# multi-rc522.net
KiCad netlist of a schematic drawn in Altium Designer
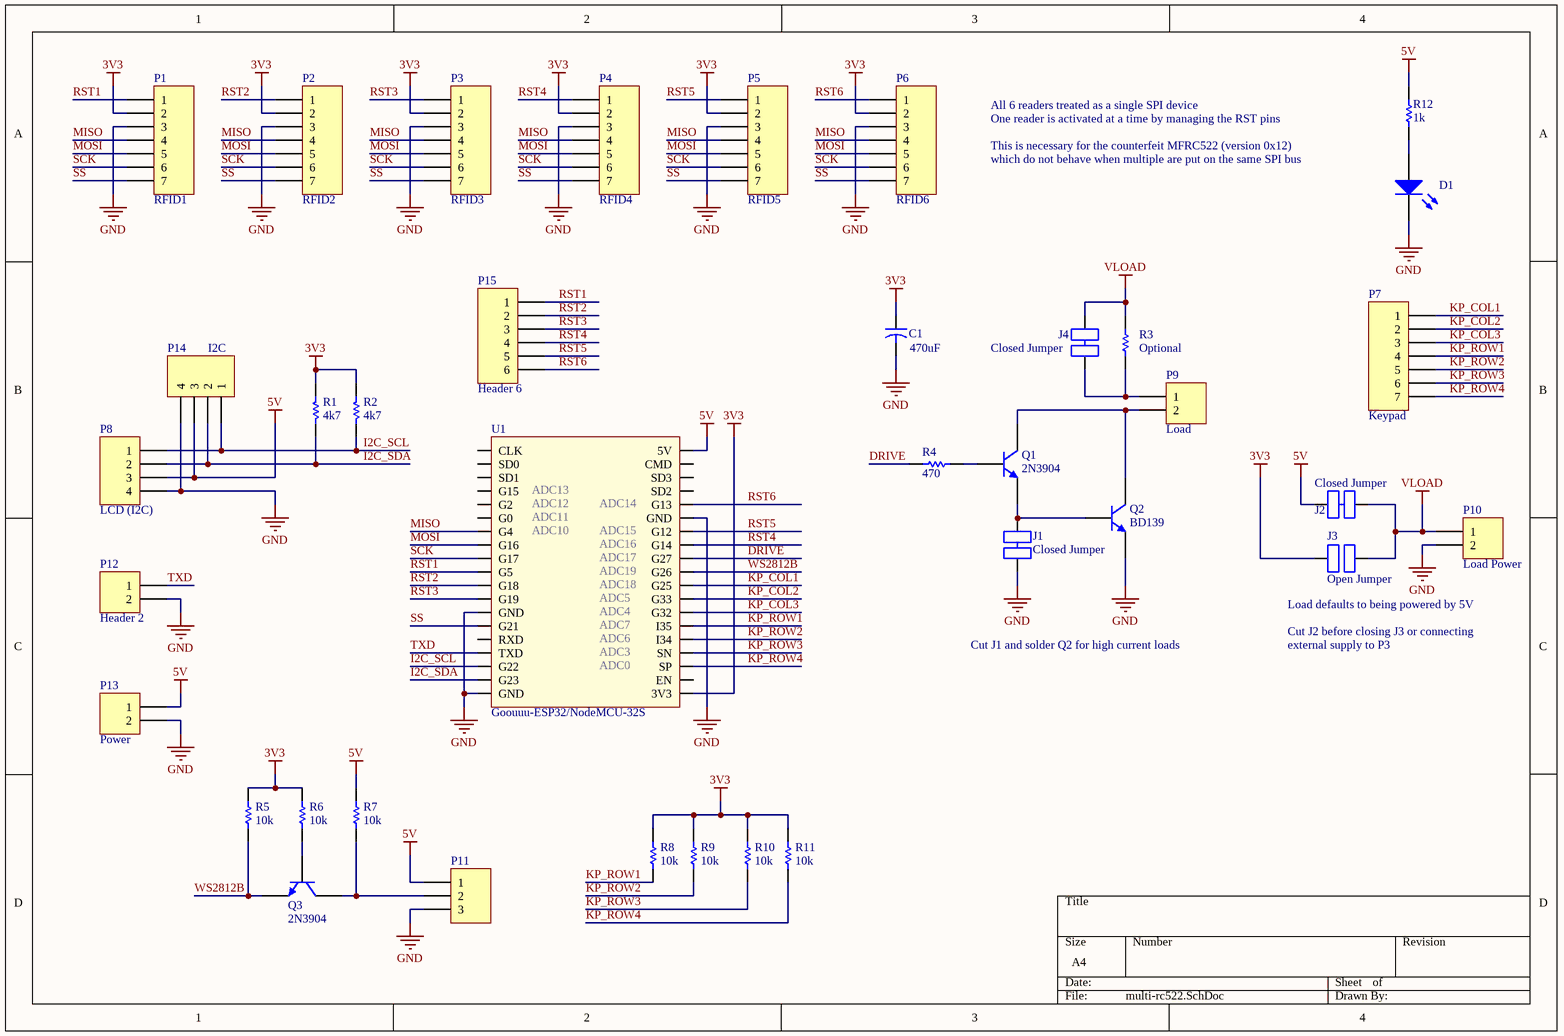
[diagram p0: multi-rc522.SchDoc]

(export (version "E")
  (design (tool "Eeschema 10.0.6"))
  (components
    (comp (ref "C1")
      (value "470uF")
      (footprint "CAPR5-4X5")
      (description "Capacitor")
      (fields (field (name "Comment") "Cap2") (field (name "PUBLISHER") "Altium Limited"))
      (libsource (lib "Miscellaneous Devices") (part "Cap2"))
    )
    (comp (ref "D1")
      (value "LED")
      (footprint "LED")
      (fields (field (name "PUBLISHER") "Altium Limited"))
      (libsource (lib "components") (part "LED"))
    )
    (comp (ref "J1")
      (value "Closed Jumper")
      (footprint "Jumper (Close)")
      (libsource (lib "components") (part "Jumper (Closed)"))
    )
    (comp (ref "J2")
      (value "Closed Jumper")
      (footprint "Jumper (Close)")
      (libsource (lib "components") (part "Jumper (Closed)"))
    )
    (comp (ref "J3")
      (value "Open Jumper")
      (footprint "Jumper (Open)")
      (libsource (lib "components") (part "Jumper (Open)"))
    )
    (comp (ref "J4")
      (value "Closed Jumper")
      (footprint "Jumper (Close)")
      (libsource (lib "components") (part "Jumper (Closed)"))
    )
    (comp (ref "P1")
      (value "RFID1")
      (footprint "HDR1X7")
      (description "Header, 7-Pin")
      (fields (field (name "PUBLISHER") "Altium Limited"))
      (libsource (lib "Miscellaneous Connectors") (part "Header 7"))
    )
    (comp (ref "P2")
      (value "RFID2")
      (footprint "HDR1X7")
      (description "Header, 7-Pin")
      (fields (field (name "PUBLISHER") "Altium Limited"))
      (libsource (lib "Miscellaneous Connectors") (part "Header 7"))
    )
    (comp (ref "P3")
      (value "RFID3")
      (footprint "HDR1X7")
      (description "Header, 7-Pin")
      (fields (field (name "PUBLISHER") "Altium Limited"))
      (libsource (lib "Miscellaneous Connectors") (part "Header 7"))
    )
    (comp (ref "P4")
      (value "RFID4")
      (footprint "HDR1X7")
      (description "Header, 7-Pin")
      (fields (field (name "PUBLISHER") "Altium Limited"))
      (libsource (lib "Miscellaneous Connectors") (part "Header 7"))
    )
    (comp (ref "P5")
      (value "RFID5")
      (footprint "HDR1X7")
      (description "Header, 7-Pin")
      (fields (field (name "PUBLISHER") "Altium Limited"))
      (libsource (lib "Miscellaneous Connectors") (part "Header 7"))
    )
    (comp (ref "P6")
      (value "RFID6")
      (footprint "HDR1X7")
      (description "Header, 7-Pin")
      (fields (field (name "PUBLISHER") "Altium Limited"))
      (libsource (lib "Miscellaneous Connectors") (part "Header 7"))
    )
    (comp (ref "P7")
      (value "Keypad")
      (footprint "HDR1X7")
      (description "Header, 7-Pin")
      (fields (field (name "PUBLISHER") "Altium Limited"))
      (libsource (lib "") (part "Header 7_1"))
    )
    (comp (ref "P8")
      (value "LCD (I2C)")
      (footprint "HDR1X4")
      (description "Header, 4-Pin")
      (fields (field (name "PUBLISHER") "Altium Limited"))
      (libsource (lib "Miscellaneous Connectors") (part "Header 4"))
    )
    (comp (ref "P9")
      (value "Load")
      (footprint "RAD-0.2")
      (description "Header, 2-Pin")
      (fields (field (name "PUBLISHER") "Altium Limited"))
      (libsource (lib "Miscellaneous Connectors") (part "Header 2"))
    )
    (comp (ref "P10")
      (value "Load Power")
      (footprint "RAD-0.2")
      (description "Header, 2-Pin")
      (fields (field (name "PUBLISHER") "Altium Limited"))
      (libsource (lib "Miscellaneous Connectors") (part "Header 2"))
    )
    (comp (ref "P11")
      (value "Header 3")
      (footprint "HDR1X3")
      (description "Header, 3-Pin")
      (fields (field (name "PUBLISHER") "Altium Limited"))
      (libsource (lib "Miscellaneous Connectors") (part "Header 3"))
    )
    (comp (ref "P12")
      (value "Header 2")
      (footprint "HDR1X2")
      (description "Header, 2-Pin")
      (fields (field (name "PUBLISHER") "Altium Limited"))
      (libsource (lib "") (part "Header 2_1"))
    )
    (comp (ref "P13")
      (value "Power")
      (footprint "RAD-0.2")
      (description "Header, 2-Pin")
      (fields (field (name "PUBLISHER") "Altium Limited"))
      (libsource (lib "") (part "Header 2_1"))
    )
    (comp (ref "P14")
      (value "I2C")
      (footprint "HDR1X4")
      (description "Header, 4-Pin")
      (fields (field (name "PUBLISHER") "Altium Limited"))
      (libsource (lib "") (part "Header 4_1"))
    )
    (comp (ref "P15")
      (value "Header 6")
      (footprint "HDR1X6")
      (description "Header, 6-Pin")
      (fields (field (name "PUBLISHER") "Altium Limited"))
      (libsource (lib "Miscellaneous Connectors") (part "Header 6"))
    )
    (comp (ref "Q1")
      (value "2N3904")
      (footprint "TO-92A")
      (description "NPN General Purpose Amplifier")
      (fields (field (name "PUBLISHER") "Altium Limited"))
      (libsource (lib "components") (part "2N3904"))
    )
    (comp (ref "Q2")
      (value "BD139")
      (footprint "Miscellaneous Devices:TO-220-AB")
      (description "NPN General Purpose Amplifier")
      (fields (field (name "PUBLISHER") "Altium Limited"))
      (libsource (lib "Miscellaneous Devices") (part "2N3904"))
    )
    (comp (ref "Q3")
      (value "2N3904")
      (footprint "TO-92A")
      (description "NPN General Purpose Amplifier")
      (fields (field (name "PUBLISHER") "Altium Limited"))
      (libsource (lib "components") (part "2N3904"))
    )
    (comp (ref "R1")
      (value "4k7")
      (footprint "Miscellaneous Devices:AXIAL-0.4")
      (description "Resistor")
      (fields (field (name "Comment") "Res1") (field (name "PUBLISHER") "Altium Limited"))
      (libsource (lib "Miscellaneous Devices") (part "Res1"))
    )
    (comp (ref "R2")
      (value "4k7")
      (footprint "Miscellaneous Devices:AXIAL-0.4")
      (description "Resistor")
      (fields (field (name "Comment") "Res1") (field (name "PUBLISHER") "Altium Limited"))
      (libsource (lib "Miscellaneous Devices") (part "Res1"))
    )
    (comp (ref "R3")
      (value "Optional")
      (footprint "Miscellaneous Devices:AXIAL-0.4")
      (description "Resistor")
      (fields (field (name "PUBLISHER") "Altium Limited"))
      (libsource (lib "Miscellaneous Devices") (part "Res1"))
    )
    (comp (ref "R4")
      (value "470")
      (footprint "Miscellaneous Devices:AXIAL-0.4")
      (description "Resistor")
      (fields (field (name "Comment") "Res1") (field (name "PUBLISHER") "Altium Limited"))
      (libsource (lib "Miscellaneous Devices") (part "Res1"))
    )
    (comp (ref "R5")
      (value "10k")
      (footprint "Miscellaneous Devices:RAD-0.1")
      (description "Resistor")
      (fields (field (name "Comment") "Res1") (field (name "PUBLISHER") "Altium Limited"))
      (libsource (lib "Miscellaneous Devices") (part "Res1"))
    )
    (comp (ref "R6")
      (value "10k")
      (footprint "Miscellaneous Devices:RAD-0.1")
      (description "Resistor")
      (fields (field (name "Comment") "Res1") (field (name "PUBLISHER") "Altium Limited"))
      (libsource (lib "Miscellaneous Devices") (part "Res1"))
    )
    (comp (ref "R7")
      (value "10k")
      (footprint "Miscellaneous Devices:RAD-0.1")
      (description "Resistor")
      (fields (field (name "Comment") "Res1") (field (name "PUBLISHER") "Altium Limited"))
      (libsource (lib "Miscellaneous Devices") (part "Res1"))
    )
    (comp (ref "R8")
      (value "10k")
      (footprint "Miscellaneous Devices:RAD-0.1")
      (description "Resistor")
      (fields (field (name "Comment") "Res1") (field (name "PUBLISHER") "Altium Limited"))
      (libsource (lib "Miscellaneous Devices") (part "Res1"))
    )
    (comp (ref "R9")
      (value "10k")
      (footprint "Miscellaneous Devices:RAD-0.1")
      (description "Resistor")
      (fields (field (name "Comment") "Res1") (field (name "PUBLISHER") "Altium Limited"))
      (libsource (lib "Miscellaneous Devices") (part "Res1"))
    )
    (comp (ref "R10")
      (value "10k")
      (footprint "Miscellaneous Devices:RAD-0.1")
      (description "Resistor")
      (fields (field (name "Comment") "Res1") (field (name "PUBLISHER") "Altium Limited"))
      (libsource (lib "Miscellaneous Devices") (part "Res1"))
    )
    (comp (ref "R11")
      (value "10k")
      (footprint "Miscellaneous Devices:RAD-0.1")
      (description "Resistor")
      (fields (field (name "Comment") "Res1") (field (name "PUBLISHER") "Altium Limited"))
      (libsource (lib "Miscellaneous Devices") (part "Res1"))
    )
    (comp (ref "R12")
      (value "1k")
      (footprint "Miscellaneous Devices:AXIAL-0.4")
      (description "Resistor")
      (fields (field (name "Comment") "Res1") (field (name "PUBLISHER") "Altium Limited"))
      (libsource (lib "Miscellaneous Devices") (part "Res1"))
    )
    (comp (ref "U1")
      (value "Goouuu-ESP32/NodeMCU-32S")
      (footprint "ESP32")
      (libsource (lib "components") (part "ESP32"))
    )
  )
  (nets
    (net (code "1") (name "/DRIVE") (class "Default")
      (node (ref "R4") (pin "2") (pinfunction "2_2") (pintype "passive"))
      (node (ref "U1") (pin "30") (pinfunction "G27_30") (pintype "passive"))
    )
    (net (code "2") (name "/I2C_SCL") (class "Default")
      (node (ref "P14") (pin "1") (pinfunction "1_1") (pintype "passive"))
      (node (ref "P8") (pin "1") (pinfunction "1_1") (pintype "passive"))
      (node (ref "R2") (pin "1") (pinfunction "1_1") (pintype "passive"))
      (node (ref "U1") (pin "17") (pinfunction "G22_17") (pintype "passive"))
    )
    (net (code "3") (name "/I2C_SDA") (class "Default")
      (node (ref "P14") (pin "2") (pinfunction "2_2") (pintype "passive"))
      (node (ref "P8") (pin "2") (pinfunction "2_2") (pintype "passive"))
      (node (ref "R1") (pin "1") (pinfunction "1_1") (pintype "passive"))
      (node (ref "U1") (pin "18") (pinfunction "G23_18") (pintype "passive"))
    )
    (net (code "4") (name "/KP_COL1") (class "Default")
      (node (ref "P7") (pin "1") (pinfunction "1_1") (pintype "passive"))
      (node (ref "U1") (pin "28") (pinfunction "G25_28") (pintype "passive"))
    )
    (net (code "5") (name "/KP_COL2") (class "Default")
      (node (ref "P7") (pin "2") (pinfunction "2_2") (pintype "passive"))
      (node (ref "U1") (pin "27") (pinfunction "G33_27") (pintype "passive"))
    )
    (net (code "6") (name "/KP_COL3") (class "Default")
      (node (ref "P7") (pin "3") (pinfunction "3_3") (pintype "passive"))
      (node (ref "U1") (pin "26") (pinfunction "G32_26") (pintype "passive"))
    )
    (net (code "7") (name "/KP_ROW1") (class "Default")
      (node (ref "P7") (pin "4") (pinfunction "4_4") (pintype "passive"))
      (node (ref "R8") (pin "1") (pinfunction "1_1") (pintype "passive"))
      (node (ref "U1") (pin "25") (pinfunction "I35_25") (pintype "passive"))
    )
    (net (code "8") (name "/KP_ROW2") (class "Default")
      (node (ref "P7") (pin "5") (pinfunction "5_5") (pintype "passive"))
      (node (ref "R9") (pin "1") (pinfunction "1_1") (pintype "passive"))
      (node (ref "U1") (pin "24") (pinfunction "I34_24") (pintype "passive"))
    )
    (net (code "9") (name "/KP_ROW3") (class "Default")
      (node (ref "P7") (pin "6") (pinfunction "6_6") (pintype "passive"))
      (node (ref "R10") (pin "1") (pinfunction "1_1") (pintype "passive"))
      (node (ref "U1") (pin "23") (pinfunction "SN_23") (pintype "passive"))
    )
    (net (code "10") (name "/KP_ROW4") (class "Default")
      (node (ref "P7") (pin "7") (pinfunction "7_7") (pintype "passive"))
      (node (ref "R11") (pin "1") (pinfunction "1_1") (pintype "passive"))
      (node (ref "U1") (pin "22") (pinfunction "SP_22") (pintype "passive"))
    )
    (net (code "11") (name "/MISO") (class "Default")
      (node (ref "P1") (pin "4") (pinfunction "4_4") (pintype "passive"))
      (node (ref "P2") (pin "4") (pinfunction "4_4") (pintype "passive"))
      (node (ref "P3") (pin "4") (pinfunction "4_4") (pintype "passive"))
      (node (ref "P4") (pin "4") (pinfunction "4_4") (pintype "passive"))
      (node (ref "P5") (pin "4") (pinfunction "4_4") (pintype "passive"))
      (node (ref "P6") (pin "4") (pinfunction "4_4") (pintype "passive"))
      (node (ref "U1") (pin "7") (pinfunction "G4_7") (pintype "passive"))
    )
    (net (code "12") (name "/MOSI") (class "Default")
      (node (ref "P1") (pin "5") (pinfunction "5_5") (pintype "passive"))
      (node (ref "P2") (pin "5") (pinfunction "5_5") (pintype "passive"))
      (node (ref "P3") (pin "5") (pinfunction "5_5") (pintype "passive"))
      (node (ref "P4") (pin "5") (pinfunction "5_5") (pintype "passive"))
      (node (ref "P5") (pin "5") (pinfunction "5_5") (pintype "passive"))
      (node (ref "P6") (pin "5") (pinfunction "5_5") (pintype "passive"))
      (node (ref "U1") (pin "8") (pinfunction "G16_8") (pintype "passive"))
    )
    (net (code "13") (name "/RST1") (class "Default")
      (node (ref "P1") (pin "1") (pinfunction "1_1") (pintype "passive"))
      (node (ref "P15") (pin "1") (pinfunction "1_1") (pintype "passive"))
      (node (ref "U1") (pin "10") (pinfunction "G5_10") (pintype "passive"))
    )
    (net (code "14") (name "/RST2") (class "Default")
      (node (ref "P15") (pin "2") (pinfunction "2_2") (pintype "passive"))
      (node (ref "P2") (pin "1") (pinfunction "1_1") (pintype "passive"))
      (node (ref "U1") (pin "11") (pinfunction "G18_11") (pintype "passive"))
    )
    (net (code "15") (name "/RST3") (class "Default")
      (node (ref "P15") (pin "3") (pinfunction "3_3") (pintype "passive"))
      (node (ref "P3") (pin "1") (pinfunction "1_1") (pintype "passive"))
      (node (ref "U1") (pin "12") (pinfunction "G19_12") (pintype "passive"))
    )
    (net (code "16") (name "/RST4") (class "Default")
      (node (ref "P15") (pin "4") (pinfunction "4_4") (pintype "passive"))
      (node (ref "P4") (pin "1") (pinfunction "1_1") (pintype "passive"))
      (node (ref "U1") (pin "31") (pinfunction "G14_31") (pintype "passive"))
    )
    (net (code "17") (name "/RST5") (class "Default")
      (node (ref "P15") (pin "5") (pinfunction "5_5") (pintype "passive"))
      (node (ref "P5") (pin "1") (pinfunction "1_1") (pintype "passive"))
      (node (ref "U1") (pin "32") (pinfunction "G12_32") (pintype "passive"))
    )
    (net (code "18") (name "/RST6") (class "Default")
      (node (ref "P15") (pin "6") (pinfunction "6_6") (pintype "passive"))
      (node (ref "P6") (pin "1") (pinfunction "1_1") (pintype "passive"))
      (node (ref "U1") (pin "34") (pinfunction "G13_34") (pintype "passive"))
    )
    (net (code "19") (name "/SCK") (class "Default")
      (node (ref "P1") (pin "6") (pinfunction "6_6") (pintype "passive"))
      (node (ref "P2") (pin "6") (pinfunction "6_6") (pintype "passive"))
      (node (ref "P3") (pin "6") (pinfunction "6_6") (pintype "passive"))
      (node (ref "P4") (pin "6") (pinfunction "6_6") (pintype "passive"))
      (node (ref "P5") (pin "6") (pinfunction "6_6") (pintype "passive"))
      (node (ref "P6") (pin "6") (pinfunction "6_6") (pintype "passive"))
      (node (ref "U1") (pin "9") (pinfunction "G17_9") (pintype "passive"))
    )
    (net (code "20") (name "/SS") (class "Default")
      (node (ref "P1") (pin "7") (pinfunction "7_7") (pintype "passive"))
      (node (ref "P2") (pin "7") (pinfunction "7_7") (pintype "passive"))
      (node (ref "P3") (pin "7") (pinfunction "7_7") (pintype "passive"))
      (node (ref "P4") (pin "7") (pinfunction "7_7") (pintype "passive"))
      (node (ref "P5") (pin "7") (pinfunction "7_7") (pintype "passive"))
      (node (ref "P6") (pin "7") (pinfunction "7_7") (pintype "passive"))
      (node (ref "U1") (pin "14") (pinfunction "G21_14") (pintype "passive"))
    )
    (net (code "21") (name "/TXD") (class "Default")
      (node (ref "P12") (pin "1") (pinfunction "1_1") (pintype "passive"))
      (node (ref "U1") (pin "16") (pinfunction "TXD_16") (pintype "passive"))
    )
    (net (code "22") (name "/WS2812B") (class "Default")
      (node (ref "Q3") (pin "1") (pinfunction "E_1") (pintype "passive"))
      (node (ref "R5") (pin "1") (pinfunction "1_1") (pintype "passive"))
      (node (ref "U1") (pin "29") (pinfunction "G26_29") (pintype "passive"))
    )
    (net (code "23") (name "3V3") (class "Default")
      (node (ref "C1") (pin "1") (pinfunction "1_1") (pintype "passive"))
      (node (ref "J3") (pin "1") (pinfunction "1_1") (pintype "passive"))
      (node (ref "P1") (pin "2") (pinfunction "2_2") (pintype "passive"))
      (node (ref "P2") (pin "2") (pinfunction "2_2") (pintype "passive"))
      (node (ref "P3") (pin "2") (pinfunction "2_2") (pintype "passive"))
      (node (ref "P4") (pin "2") (pinfunction "2_2") (pintype "passive"))
      (node (ref "P5") (pin "2") (pinfunction "2_2") (pintype "passive"))
      (node (ref "P6") (pin "2") (pinfunction "2_2") (pintype "passive"))
      (node (ref "R1") (pin "2") (pinfunction "2_2") (pintype "passive"))
      (node (ref "R10") (pin "2") (pinfunction "2_2") (pintype "passive"))
      (node (ref "R11") (pin "2") (pinfunction "2_2") (pintype "passive"))
      (node (ref "R2") (pin "2") (pinfunction "2_2") (pintype "passive"))
      (node (ref "R5") (pin "2") (pinfunction "2_2") (pintype "passive"))
      (node (ref "R6") (pin "2") (pinfunction "2_2") (pintype "passive"))
      (node (ref "R8") (pin "2") (pinfunction "2_2") (pintype "passive"))
      (node (ref "R9") (pin "2") (pinfunction "2_2") (pintype "passive"))
      (node (ref "U1") (pin "20") (pinfunction "3V3_20") (pintype "power_in"))
    )
    (net (code "24") (name "5V") (class "Default")
      (node (ref "J2") (pin "1") (pinfunction "1_1") (pintype "passive"))
      (node (ref "P11") (pin "1") (pinfunction "1_1") (pintype "passive"))
      (node (ref "P13") (pin "1") (pinfunction "1_1") (pintype "passive"))
      (node (ref "P14") (pin "3") (pinfunction "3_3") (pintype "passive"))
      (node (ref "P8") (pin "3") (pinfunction "3_3") (pintype "passive"))
      (node (ref "R12") (pin "1") (pinfunction "1_1") (pintype "passive"))
      (node (ref "R7") (pin "2") (pinfunction "2_2") (pintype "passive"))
      (node (ref "U1") (pin "38") (pinfunction "5V_38") (pintype "power_in"))
    )
    (net (code "25") (name "GND") (class "Default")
      (node (ref "C1") (pin "2") (pinfunction "2_2") (pintype "passive"))
      (node (ref "D1") (pin "2") (pinfunction "K_2") (pintype "passive"))
      (node (ref "J1") (pin "2") (pinfunction "2_2") (pintype "passive"))
      (node (ref "P1") (pin "3") (pinfunction "3_3") (pintype "passive"))
      (node (ref "P10") (pin "2") (pinfunction "2_2") (pintype "passive"))
      (node (ref "P11") (pin "3") (pinfunction "3_3") (pintype "passive"))
      (node (ref "P12") (pin "2") (pinfunction "2_2") (pintype "passive"))
      (node (ref "P13") (pin "2") (pinfunction "2_2") (pintype "passive"))
      (node (ref "P14") (pin "4") (pinfunction "4_4") (pintype "passive"))
      (node (ref "P2") (pin "3") (pinfunction "3_3") (pintype "passive"))
      (node (ref "P3") (pin "3") (pinfunction "3_3") (pintype "passive"))
      (node (ref "P4") (pin "3") (pinfunction "3_3") (pintype "passive"))
      (node (ref "P5") (pin "3") (pinfunction "3_3") (pintype "passive"))
      (node (ref "P6") (pin "3") (pinfunction "3_3") (pintype "passive"))
      (node (ref "P8") (pin "4") (pinfunction "4_4") (pintype "passive"))
      (node (ref "Q2") (pin "1") (pinfunction "E_1") (pintype "passive"))
      (node (ref "U1") (pin "13") (pinfunction "GND_13") (pintype "power_in"))
      (node (ref "U1") (pin "19") (pinfunction "GND_19") (pintype "power_in"))
      (node (ref "U1") (pin "33") (pinfunction "GND_33") (pintype "power_in"))
    )
    (net (code "26") (name "Net-(D1-A)") (class "Default")
      (node (ref "D1") (pin "1") (pinfunction "A_1") (pintype "passive"))
      (node (ref "R12") (pin "2") (pinfunction "2_2") (pintype "passive"))
    )
    (net (code "27") (name "Net-(J4-Pad1)") (class "Default")
      (node (ref "J4") (pin "1") (pinfunction "1_1") (pintype "passive"))
      (node (ref "P9") (pin "1") (pinfunction "1_1") (pintype "passive"))
      (node (ref "R3") (pin "2") (pinfunction "2_2") (pintype "passive"))
    )
    (net (code "28") (name "Net-(Q1-B)") (class "Default")
      (node (ref "Q1") (pin "2") (pinfunction "B_2") (pintype "passive"))
      (node (ref "R4") (pin "1") (pinfunction "1_1") (pintype "passive"))
    )
    (net (code "29") (name "Net-(Q1-C)") (class "Default")
      (node (ref "P9") (pin "2") (pinfunction "2_2") (pintype "passive"))
      (node (ref "Q1") (pin "3") (pinfunction "C_3") (pintype "passive"))
      (node (ref "Q2") (pin "3") (pinfunction "C_3") (pintype "passive"))
    )
    (net (code "30") (name "Net-(Q1-E)") (class "Default")
      (node (ref "J1") (pin "1") (pinfunction "1_1") (pintype "passive"))
      (node (ref "Q1") (pin "1") (pinfunction "E_1") (pintype "passive"))
      (node (ref "Q2") (pin "2") (pinfunction "B_2") (pintype "passive"))
    )
    (net (code "31") (name "Net-(Q3-B)") (class "Default")
      (node (ref "Q3") (pin "2") (pinfunction "B_2") (pintype "passive"))
      (node (ref "R6") (pin "1") (pinfunction "1_1") (pintype "passive"))
    )
    (net (code "32") (name "Net-(Q3-C)") (class "Default")
      (node (ref "P11") (pin "2") (pinfunction "2_2") (pintype "passive"))
      (node (ref "Q3") (pin "3") (pinfunction "C_3") (pintype "passive"))
      (node (ref "R7") (pin "1") (pinfunction "1_1") (pintype "passive"))
    )
    (net (code "33") (name "VLOAD") (class "Default")
      (node (ref "J2") (pin "2") (pinfunction "2_2") (pintype "passive"))
      (node (ref "J3") (pin "2") (pinfunction "2_2") (pintype "passive"))
      (node (ref "J4") (pin "2") (pinfunction "2_2") (pintype "passive"))
      (node (ref "P10") (pin "1") (pinfunction "1_1") (pintype "passive"))
      (node (ref "R3") (pin "1") (pinfunction "1_1") (pintype "passive"))
    )
    (net (code "34") (name "unconnected-(U1-CLK-Pad1)") (class "Default")
      (node (ref "U1") (pin "1") (pinfunction "CLK_1") (pintype "passive"))
    )
    (net (code "35") (name "unconnected-(U1-CMD-Pad37)") (class "Default")
      (node (ref "U1") (pin "37") (pinfunction "CMD_37") (pintype "passive"))
    )
    (net (code "36") (name "unconnected-(U1-EN-Pad21)") (class "Default")
      (node (ref "U1") (pin "21") (pinfunction "EN_21") (pintype "passive"))
    )
    (net (code "37") (name "unconnected-(U1-G0-Pad6)") (class "Default")
      (node (ref "U1") (pin "6") (pinfunction "G0_6") (pintype "passive"))
    )
    (net (code "38") (name "unconnected-(U1-G2-Pad5)") (class "Default")
      (node (ref "U1") (pin "5") (pinfunction "G2_5") (pintype "passive"))
    )
    (net (code "39") (name "unconnected-(U1-G15-Pad4)") (class "Default")
      (node (ref "U1") (pin "4") (pinfunction "G15_4") (pintype "passive"))
    )
    (net (code "40") (name "unconnected-(U1-RXD-Pad15)") (class "Default")
      (node (ref "U1") (pin "15") (pinfunction "RXD_15") (pintype "passive"))
    )
    (net (code "41") (name "unconnected-(U1-SD0-Pad2)") (class "Default")
      (node (ref "U1") (pin "2") (pinfunction "SD0_2") (pintype "passive"))
    )
    (net (code "42") (name "unconnected-(U1-SD1-Pad3)") (class "Default")
      (node (ref "U1") (pin "3") (pinfunction "SD1_3") (pintype "passive"))
    )
    (net (code "43") (name "unconnected-(U1-SD2-Pad35)") (class "Default")
      (node (ref "U1") (pin "35") (pinfunction "SD2_35") (pintype "passive"))
    )
    (net (code "44") (name "unconnected-(U1-SD3-Pad36)") (class "Default")
      (node (ref "U1") (pin "36") (pinfunction "SD3_36") (pintype "passive"))
    )
  )
)
